# lps_display_rev_10_p1.net
KiCad netlist of a schematic drawn in Altium Designer
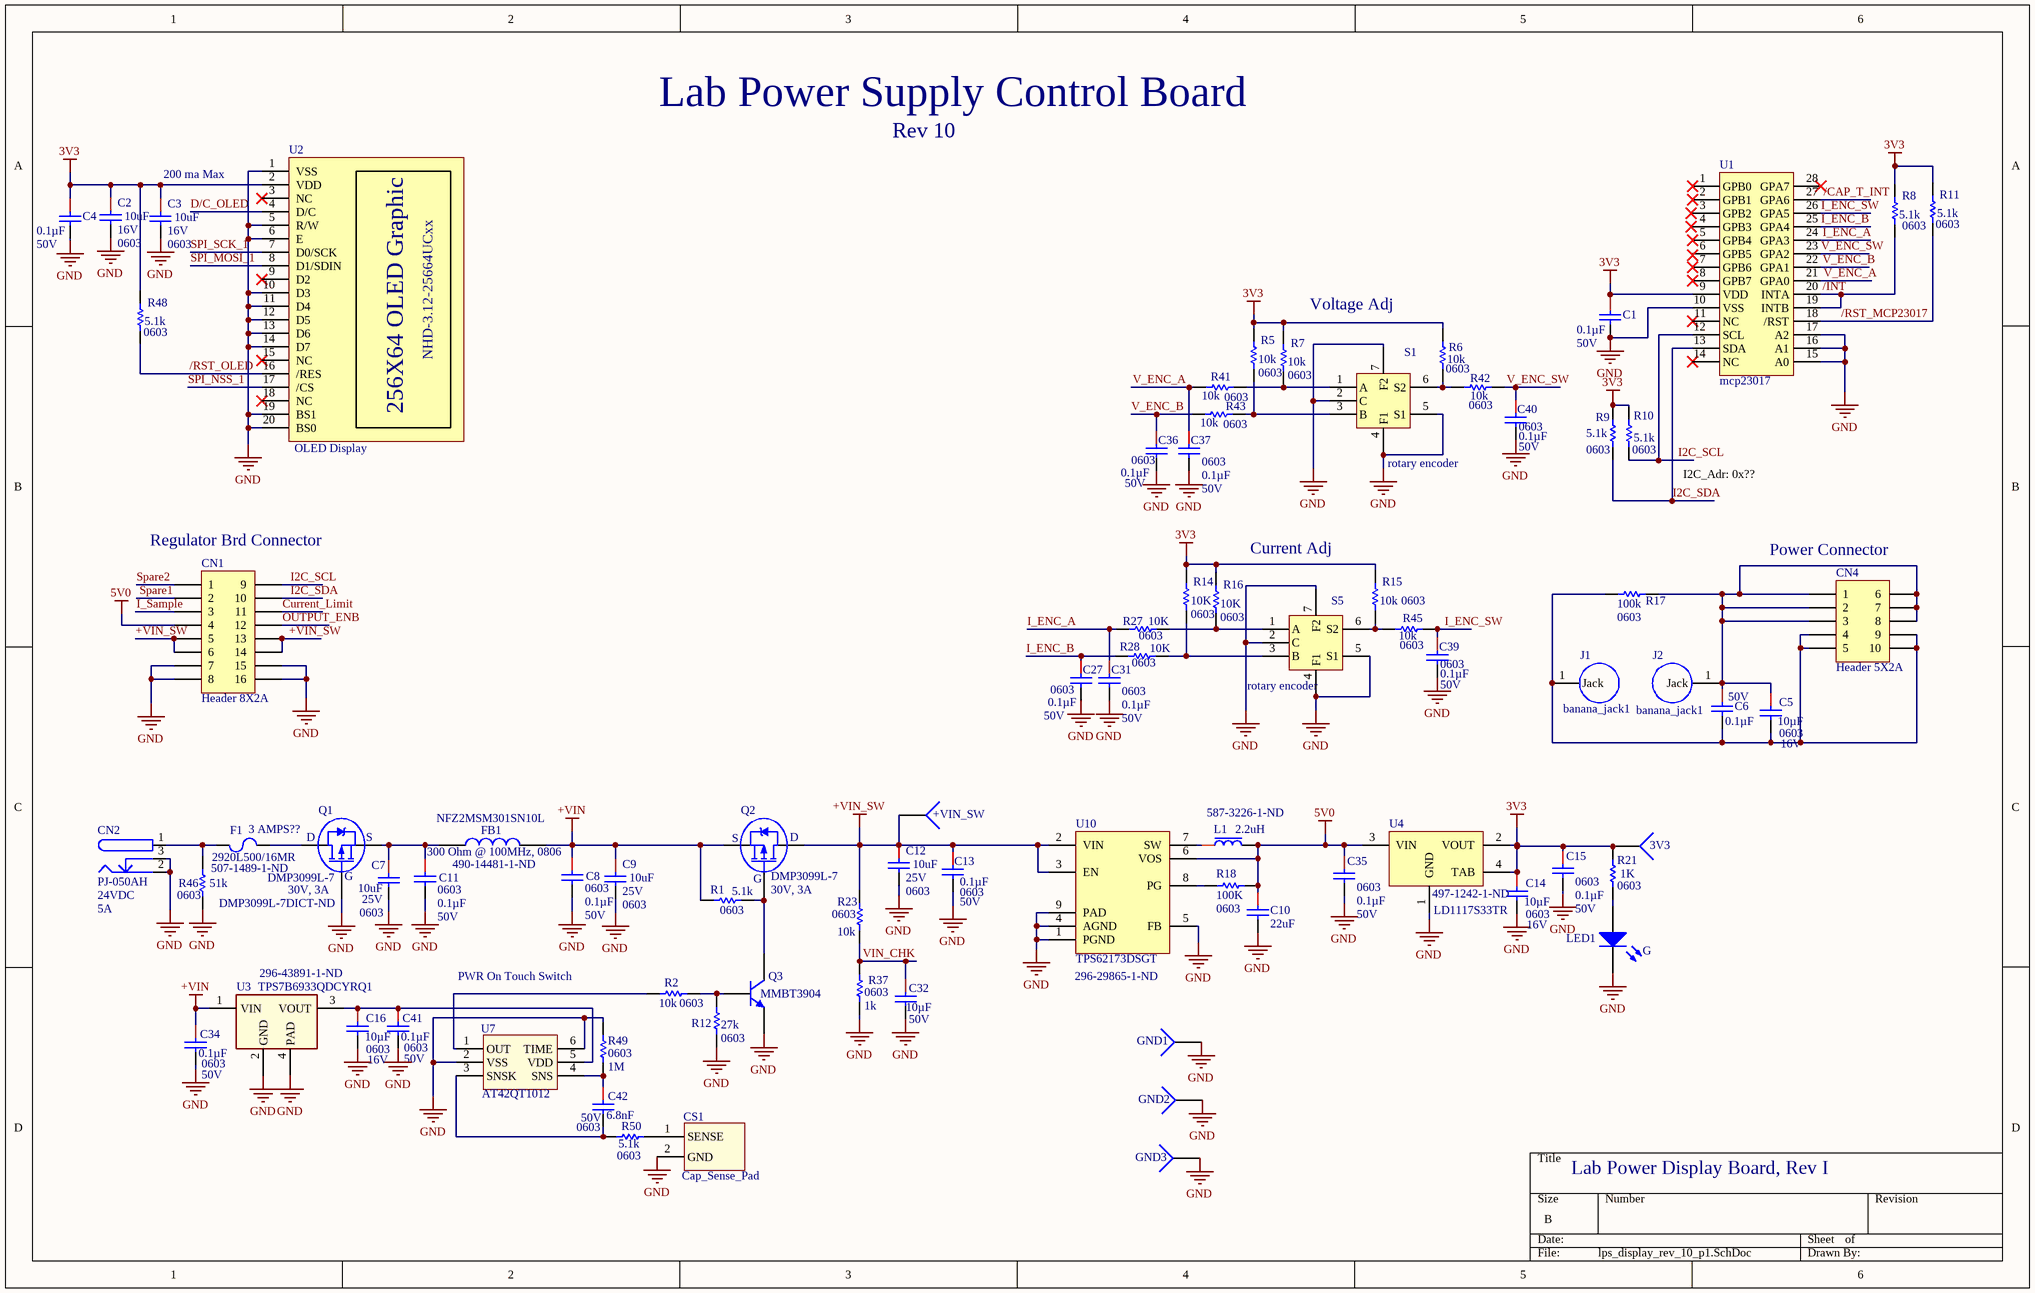
[diagram p0: lps_display_rev_10_p1.SchDoc]

(export (version "E")
  (design (tool "Eeschema 10.0.6"))
  (components
    (comp (ref "+VIN_SW")
      (value "~")
      (footprint "TestPoint-TH 35 mil")
      (description "Test Point")
      (libsource (lib "OLogic-Misc") (part "TestPoint"))
    )
    (comp (ref "3V3")
      (value "~")
      (footprint "TestPoint-TH 35 mil")
      (description "Test Point")
      (libsource (lib "OLogic-Misc") (part "TestPoint"))
    )
    (comp (ref "C1")
      (value "0.1uF 0603 50V")
      (footprint "CAPC0603(1608)_N")
      (fields
        (field (name "MANUFACTURER") "Kemet")
        (field (name "MANUFACTURER PART NUMBER") "C0603C104K5RACTU")
        (field (name "TOLERANCE") "±10%")
        (field (name "CAPACITANCE") "0.1µF")
        (field (name "VOLTAGE - RATED") "50V")
      )
      (libsource (lib "OLogic-Passive") (part "CAP CER 0.1UF 50V 10% X7R 0603"))
    )
    (comp (ref "C2")
      (value "10uF")
      (footprint "CAPC0603(1608)_N")
      (description "10UF 0603 16V")
      (fields
        (field (name "MANUFACTURER") "Murata Electronics North America")
        (field (name "MANUFACTURER PART NUMBER") "GRM188R61C106MA73D")
        (field (name "PACKAGE / CASE") "0603")
        (field (name "VOLTAGE - RATED") "16V")
      )
      (libsource (lib "OLogic-Passive") (part "CAP CER 10UF 16V 20% X5R 0603"))
    )
    (comp (ref "C3")
      (value "10uF")
      (footprint "CAPC0603(1608)_N")
      (description "10UF 0603 16V")
      (fields
        (field (name "MANUFACTURER") "Murata Electronics North America")
        (field (name "MANUFACTURER PART NUMBER") "GRM188R61C106MA73D")
        (field (name "PACKAGE / CASE") "0603")
        (field (name "VOLTAGE - RATED") "16V")
      )
      (libsource (lib "OLogic-Passive") (part "CAP CER 10UF 16V 20% X5R 0603"))
    )
    (comp (ref "C4")
      (value "0.1uF 0603 50V")
      (footprint "CAPC0603(1608)_N")
      (fields
        (field (name "MANUFACTURER") "Kemet")
        (field (name "MANUFACTURER PART NUMBER") "C0603C104K5RACTU")
        (field (name "TOLERANCE") "±10%")
        (field (name "CAPACITANCE") "0.1µF")
        (field (name "VOLTAGE - RATED") "50V")
      )
      (libsource (lib "OLogic-Passive") (part "CAP CER 0.1UF 50V 10% X7R 0603"))
    )
    (comp (ref "C5")
      (value "10uF")
      (footprint "CAPC0603(1608)_N")
      (description "10UF 0603 16V")
      (fields
        (field (name "MANUFACTURER") "Murata Electronics North America")
        (field (name "MANUFACTURER PART NUMBER") "GRM188R61C106MA73D")
        (field (name "CAPACITANCE") "10µF")
        (field (name "PACKAGE / CASE") "0603")
        (field (name "VOLTAGE - RATED") "16V")
      )
      (libsource (lib "OLogic-Passive") (part "CAP CER 10UF 16V 20% X5R 0603"))
    )
    (comp (ref "C6")
      (value "0.1uF 0603 50V")
      (footprint "CAPC0603(1608)_N")
      (fields
        (field (name "MANUFACTURER") "Kemet")
        (field (name "MANUFACTURER PART NUMBER") "C0603C104K5RACTU")
        (field (name "TOLERANCE") "±10%")
        (field (name "CAPACITANCE") "0.1µF")
        (field (name "VOLTAGE - RATED") "50V")
      )
      (libsource (lib "OLogic-Passive") (part "CAP CER 0.1UF 50V 10% X7R 0603"))
    )
    (comp (ref "C7")
      (value "10uF")
      (footprint "CAPC0603(1608)_N")
      (description "10UF 0603 16V")
      (fields
        (field (name "MANUFACTURER") "Murata Electronics North America")
        (field (name "MANUFACTURER PART NUMBER") "GRM188R61C106MA73D")
        (field (name "PACKAGE / CASE") "0603")
        (field (name "VOLTAGE - RATED") "25V")
      )
      (libsource (lib "OLogic-Passive") (part "CAP CER 10UF 16V 20% X5R 0603"))
    )
    (comp (ref "C8")
      (value "0.1uF 0603 50V")
      (footprint "CAPC0603(1608)_N")
      (fields
        (field (name "MANUFACTURER") "Yageo")
        (field (name "MANUFACTURER PART NUMBER") "CC0603ZRY5V9BB104")
        (field (name "TOLERANCE") "-20%, +80%")
        (field (name "PACKAGE / CASE") "0603")
        (field (name "CAPACITANCE") "0.1µF")
        (field (name "VOLTAGE - RATED") "50V")
      )
      (libsource (lib "OLogic-Passive") (part "CAP CER 0.1UF 50V 10% X7R 0603"))
    )
    (comp (ref "C9")
      (value "10uF")
      (footprint "CAPC0603(1608)_N")
      (description "10UF 0603 16V")
      (fields
        (field (name "MANUFACTURER") "Murata Electronics North America")
        (field (name "MANUFACTURER PART NUMBER") "GRM188R61C106MA73D")
        (field (name "PACKAGE / CASE") "0603")
        (field (name "VOLTAGE - RATED") "25V")
      )
      (libsource (lib "OLogic-Passive") (part "CAP CER 10UF 16V 20% X5R 0603"))
    )
    (comp (ref "C10")
      (value "22uF")
      (footprint "CAPC0603(1608)_M")
      (description "CAP CER 22UF 10V 20% 0603")
      (fields (field (name "TOLERANCE") "20%"))
      (libsource (lib "OLogic Nexus Vault") (part "=Capacitance"))
    )
    (comp (ref "C11")
      (value "0.1uF 0603 50V")
      (footprint "CAPC0603(1608)_N")
      (fields
        (field (name "MANUFACTURER") "Yageo")
        (field (name "MANUFACTURER PART NUMBER") "CC0603ZRY5V9BB104")
        (field (name "TOLERANCE") "-20%, +80%")
        (field (name "PACKAGE / CASE") "0603")
        (field (name "CAPACITANCE") "0.1µF")
        (field (name "VOLTAGE - RATED") "50V")
      )
      (libsource (lib "OLogic-Passive") (part "CAP CER 0.1UF 50V 10% X7R 0603"))
    )
    (comp (ref "C12")
      (value "10uF")
      (footprint "CAPC0603(1608)_N")
      (description "10UF 0603 16V")
      (fields
        (field (name "MANUFACTURER") "Murata Electronics North America")
        (field (name "MANUFACTURER PART NUMBER") "GRM188R61C106MA73D")
        (field (name "PACKAGE / CASE") "0603")
        (field (name "VOLTAGE - RATED") "25V")
      )
      (libsource (lib "OLogic-Passive") (part "CAP CER 10UF 16V 20% X5R 0603"))
    )
    (comp (ref "C13")
      (value "0.1uF 0603 50V")
      (footprint "CAPC0603(1608)_N")
      (fields
        (field (name "MANUFACTURER") "Yageo")
        (field (name "MANUFACTURER PART NUMBER") "CC0603ZRY5V9BB104")
        (field (name "TOLERANCE") "-20%, +80%")
        (field (name "PACKAGE / CASE") "0603")
        (field (name "CAPACITANCE") "0.1µF")
        (field (name "VOLTAGE - RATED") "50V")
      )
      (libsource (lib "OLogic-Passive") (part "CAP CER 0.1UF 50V 10% X7R 0603"))
    )
    (comp (ref "C14")
      (value "10uF")
      (footprint "CAPC0603(1608)_N")
      (description "10UF 0603 16V")
      (fields
        (field (name "MANUFACTURER") "Murata Electronics North America")
        (field (name "MANUFACTURER PART NUMBER") "GRM188R61C106MA73D")
        (field (name "CAPACITANCE") "10µF")
        (field (name "PACKAGE / CASE") "0603")
        (field (name "VOLTAGE - RATED") "16V")
      )
      (libsource (lib "OLogic-Passive") (part "CAP CER 10UF 16V 20% X5R 0603"))
    )
    (comp (ref "C15")
      (value "0.1uF 0603 50V")
      (footprint "CAPC0603(1608)_N")
      (fields
        (field (name "MANUFACTURER") "Yageo")
        (field (name "MANUFACTURER PART NUMBER") "CC0603ZRY5V9BB104")
        (field (name "TOLERANCE") "-20%, +80%")
        (field (name "PACKAGE / CASE") "0603")
        (field (name "CAPACITANCE") "0.1µF")
        (field (name "VOLTAGE - RATED") "50V")
      )
      (libsource (lib "OLogic-Passive") (part "CAP CER 0.1UF 50V 10% X7R 0603"))
    )
    (comp (ref "C16")
      (value "10uF")
      (footprint "CAPC0603(1608)_N")
      (description "10UF 0603 16V")
      (fields
        (field (name "MANUFACTURER") "Murata Electronics North America")
        (field (name "MANUFACTURER PART NUMBER") "GRM188R61C106MA73D")
        (field (name "CAPACITANCE") "10µF")
        (field (name "PACKAGE / CASE") "0603")
        (field (name "VOLTAGE - RATED") "16V")
      )
      (libsource (lib "OLogic-Passive") (part "CAP CER 10UF 16V 20% X5R 0603"))
    )
    (comp (ref "C27")
      (value "0.1uF 0603 50V")
      (footprint "CAPC0603(1608)_N")
      (fields
        (field (name "MANUFACTURER") "Yageo")
        (field (name "MANUFACTURER PART NUMBER") "CC0603ZRY5V9BB104")
        (field (name "TOLERANCE") "-20%, +80%")
        (field (name "PACKAGE / CASE") "0603")
        (field (name "CAPACITANCE") "0.1µF")
        (field (name "VOLTAGE - RATED") "50V")
      )
      (libsource (lib "OLogic-Passive") (part "CAP CER 0.1UF 50V 10% X7R 0603"))
    )
    (comp (ref "C31")
      (value "0.1uF 0603 50V")
      (footprint "CAPC0603(1608)_N")
      (fields
        (field (name "MANUFACTURER") "Yageo")
        (field (name "MANUFACTURER PART NUMBER") "CC0603ZRY5V9BB104")
        (field (name "TOLERANCE") "-20%, +80%")
        (field (name "PACKAGE / CASE") "0603")
        (field (name "CAPACITANCE") "0.1µF")
        (field (name "VOLTAGE - RATED") "50V")
      )
      (libsource (lib "OLogic-Passive") (part "CAP CER 0.1UF 50V 10% X7R 0603"))
    )
    (comp (ref "C32")
      (value "0.1uF 0603 50V")
      (footprint "CAPC0603(1608)_N")
      (fields
        (field (name "MANUFACTURER") "Kemet")
        (field (name "MANUFACTURER PART NUMBER") "C0603C104K5RACTU")
        (field (name "TOLERANCE") "±10%")
        (field (name "CAPACITANCE") "10µF")
        (field (name "VOLTAGE - RATED") "50V")
      )
      (libsource (lib "OLogic-Passive") (part "CAP CER 0.1UF 50V 10% X7R 0603"))
    )
    (comp (ref "C34")
      (value "0.1uF 0603 50V")
      (footprint "CAPC0603(1608)_N")
      (fields
        (field (name "MANUFACTURER") "Yageo")
        (field (name "MANUFACTURER PART NUMBER") "CC0603ZRY5V9BB104")
        (field (name "TOLERANCE") "-20%, +80%")
        (field (name "PACKAGE / CASE") "0603")
        (field (name "CAPACITANCE") "0.1µF")
        (field (name "VOLTAGE - RATED") "50V")
      )
      (libsource (lib "OLogic-Passive") (part "CAP CER 0.1UF 50V 10% X7R 0603"))
    )
    (comp (ref "C35")
      (value "0.1uF 0603 50V")
      (footprint "CAPC0603(1608)_N")
      (fields
        (field (name "MANUFACTURER") "Yageo")
        (field (name "MANUFACTURER PART NUMBER") "CC0603ZRY5V9BB104")
        (field (name "TOLERANCE") "-20%, +80%")
        (field (name "PACKAGE / CASE") "0603")
        (field (name "CAPACITANCE") "0.1µF")
        (field (name "VOLTAGE - RATED") "50V")
      )
      (libsource (lib "OLogic-Passive") (part "CAP CER 0.1UF 50V 10% X7R 0603"))
    )
    (comp (ref "C36")
      (value "0.1uF 0603 50V")
      (footprint "CAPC0603(1608)_N")
      (fields
        (field (name "MANUFACTURER") "Yageo")
        (field (name "MANUFACTURER PART NUMBER") "CC0603ZRY5V9BB104")
        (field (name "TOLERANCE") "-20%, +80%")
        (field (name "PACKAGE / CASE") "0603")
        (field (name "CAPACITANCE") "0.1µF")
        (field (name "VOLTAGE - RATED") "50V")
      )
      (libsource (lib "OLogic-Passive") (part "CAP CER 0.1UF 50V 10% X7R 0603"))
    )
    (comp (ref "C37")
      (value "0.1uF 0603 50V")
      (footprint "CAPC0603(1608)_N")
      (fields
        (field (name "MANUFACTURER") "Yageo")
        (field (name "MANUFACTURER PART NUMBER") "CC0603ZRY5V9BB104")
        (field (name "TOLERANCE") "-20%, +80%")
        (field (name "PACKAGE / CASE") "0603")
        (field (name "CAPACITANCE") "0.1µF")
        (field (name "VOLTAGE - RATED") "50V")
      )
      (libsource (lib "OLogic-Passive") (part "CAP CER 0.1UF 50V 10% X7R 0603"))
    )
    (comp (ref "C39")
      (value "0.1uF 0603 50V")
      (footprint "CAPC0603(1608)_N")
      (fields
        (field (name "MANUFACTURER") "Yageo")
        (field (name "MANUFACTURER PART NUMBER") "CC0603ZRY5V9BB104")
        (field (name "TOLERANCE") "-20%, +80%")
        (field (name "PACKAGE / CASE") "0603")
        (field (name "CAPACITANCE") "0.1µF")
        (field (name "VOLTAGE - RATED") "50V")
      )
      (libsource (lib "OLogic-Passive") (part "CAP CER 0.1UF 50V 10% X7R 0603"))
    )
    (comp (ref "C40")
      (value "0.1uF 0603 50V")
      (footprint "CAPC0603(1608)_N")
      (fields
        (field (name "MANUFACTURER") "Yageo")
        (field (name "MANUFACTURER PART NUMBER") "CC0603ZRY5V9BB104")
        (field (name "TOLERANCE") "-20%, +80%")
        (field (name "PACKAGE / CASE") "0603")
        (field (name "CAPACITANCE") "0.1µF")
        (field (name "VOLTAGE - RATED") "50V")
      )
      (libsource (lib "OLogic-Passive") (part "CAP CER 0.1UF 50V 10% X7R 0603"))
    )
    (comp (ref "C41")
      (value "0.1uF 0603 50V")
      (footprint "CAPC0603(1608)_N")
      (fields
        (field (name "MANUFACTURER") "Yageo")
        (field (name "MANUFACTURER PART NUMBER") "CC0603ZRY5V9BB104")
        (field (name "TOLERANCE") "-20%, +80%")
        (field (name "PACKAGE / CASE") "0603")
        (field (name "CAPACITANCE") "0.1µF")
        (field (name "VOLTAGE - RATED") "50V")
      )
      (libsource (lib "OLogic-Passive") (part "CAP CER 0.1UF 50V 10% X7R 0603"))
    )
    (comp (ref "C42")
      (value "0.1uF 0603 50V")
      (footprint "CAPC0603(1608)_N")
      (fields
        (field (name "MANUFACTURER") "Yageo")
        (field (name "MANUFACTURER PART NUMBER") "CC0603ZRY5V9BB104")
        (field (name "TOLERANCE") "-20%, +80%")
        (field (name "PACKAGE / CASE") "0603")
        (field (name "CAPACITANCE") "6.8nF")
        (field (name "VOLTAGE - RATED") "50V")
      )
      (libsource (lib "OLogic-Passive") (part "CAP CER 0.1UF 50V 10% X7R 0603"))
    )
    (comp (ref "CN1")
      (value "Header 8X2A")
      (footprint "HDR2X8_CEN")
      (description "Header, 8-Pin, Dual row")
      (fields (field (name "PUBLISHER") "Altium Limited"))
      (libsource (lib "OLogic Nexus Vault") (part "Header 8X2A"))
    )
    (comp (ref "CN2")
      (value "PJ-050AH")
      (footprint "PJ-050AH")
      (description "Power Barrel Connector Jack 2.00mm ID 5.50mm OD Through Hole, Right Angle")
      (fields
        (field (name "VOLTAGE - RATED") "24VDC")
        (field (name "CURRENT RATING") "5A")
        (field (name "MANUFACTURER") "CUI")
      )
      (libsource (lib "OLogic Nexus Vault") (part "PJ-050AH"))
    )
    (comp (ref "CN4")
      (value "Header 5X2A")
      (footprint "HDR2X5_CEN")
      (description "Header, 5-Pin, Dual row")
      (fields (field (name "PUBLISHER") "Altium Limited"))
      (libsource (lib "OLogic Nexus Vault") (part "Header 5X2A"))
    )
    (comp (ref "CS1")
      (value "Cap_Sense_Pad")
      (footprint "CAP_TOUCH_ROUND")
      (libsource (lib "*") (part "Cap_Sense_Pad"))
    )
    (comp (ref "F1")
      (value "2920L500/16MR")
      (footprint "2920 Fuse")
      (description "PTC RESET FUSE 16V 5A 2920")
      (libsource (lib "OLogic Nexus Vault") (part "FUSE_GENERIC"))
    )
    (comp (ref "FB1")
      (value "300 Ohm @ 100MHz, 0806")
      (footprint "RESC0805(2012)_M")
      (description "40 OHM 0805 1.5A")
      (fields
        (field (name "MANUFACTURER") "Laird-Signal Integrity Products")
        (field (name "MANUFACTURER PART NUMBER") "MI0805K400R-10")
        (field (name "CREATOR") "osman")
      )
      (libsource (lib "OLogic-Passive") (part "FERRITE 40 OHM 1.5A 0805"))
    )
    (comp (ref "GND1")
      (value "~")
      (footprint "TestPoint-TH 35 mil")
      (description "Test Point")
      (libsource (lib "OLogic-Misc") (part "TestPoint"))
    )
    (comp (ref "GND2")
      (value "~")
      (footprint "TestPoint-TH 35 mil")
      (description "Test Point")
      (libsource (lib "OLogic-Misc") (part "TestPoint"))
    )
    (comp (ref "GND3")
      (value "~")
      (footprint "TestPoint-TH 35 mil")
      (description "Test Point")
      (libsource (lib "OLogic-Misc") (part "TestPoint"))
    )
    (comp (ref "J1")
      (value "banana_jack1")
      (footprint "Banana_jack1")
      (libsource (lib "lab power supply") (part "banana_jack1"))
    )
    (comp (ref "J2")
      (value "banana_jack1")
      (footprint "Banana_jack1")
      (libsource (lib "lab power supply") (part "banana_jack1"))
    )
    (comp (ref "L1")
      (value "2.2uH")
      (footprint "INDC2520X10N")
      (description "FIXED IND 2.2UH 1.9A 117 MOHM")
      (fields (field (name "TOLERANCE") "20%"))
      (libsource (lib "OLogic Nexus Vault") (part "IND_GENERIC"))
    )
    (comp (ref "LED1")
      (value "G")
      (footprint "SM-LED-0603")
      (description "0603 SMD LED")
      (libsource (lib "OLogic-Diode-Opto-LED") (part "0603 LED"))
    )
    (comp (ref "Q1")
      (value "DMP3099L-7")
      (footprint "SOT23")
      (description "DMP3099L-7 MOSFET P-CH SOT23")
      (fields (field (name "MANUFACTURER") "Diodes Incorporated") (field (name "TEXT") "30V, 3A"))
      (libsource (lib "") (part "DMP3099L-7_1"))
    )
    (comp (ref "Q2")
      (value "DMP3099L-7")
      (footprint "SOT23")
      (description "DMP3099L-7 MOSFET P-CH SOT23")
      (fields (field (name "MANUFACTURER") "Diodes Incorporated") (field (name "TEXT") "30V, 3A"))
      (libsource (lib "OLogic-Trans-Drivers") (part "DMP3099L-7"))
    )
    (comp (ref "Q3")
      (value "MMBT3904")
      (footprint "SOT23")
      (description "MMBT3904 NPN")
      (fields (field (name "MANUFACTURER") "ON Semiconductor") (field (name "MPN") "MMBT3904WT1G"))
      (libsource (lib "OLogic-Trans-Drivers") (part "MMBT3904"))
    )
    (comp (ref "R1")
      (value "4.7K")
      (footprint "RESC0603(1608)_N")
      (description "4.7K 0603")
      (fields
        (field (name "MANUFACTURER") "Panasonic Electronic Components")
        (field (name "MANUFACTURER PART NUMBER") "ERJ-3GEYJ472V")
        (field (name "RESISTANCE (OHMS)") "5.1k")
        (field (name "PACKAGE / CASE") "0603")
      )
      (libsource (lib "OLogic-Passive") (part "RES 4.7K OHM 1/10W 5% 0603 SMD"))
    )
    (comp (ref "R2")
      (value "4.7K")
      (footprint "RESC0603(1608)_N")
      (description "4.7K 0603")
      (fields
        (field (name "MANUFACTURER") "Panasonic Electronic Components")
        (field (name "MANUFACTURER PART NUMBER") "ERJ-3GEYJ472V")
        (field (name "RESISTANCE (OHMS)") "10k")
        (field (name "PACKAGE / CASE") "0603")
      )
      (libsource (lib "OLogic-Passive") (part "RES 4.7K OHM 1/10W 5% 0603 SMD"))
    )
    (comp (ref "R5")
      (value "4.7K")
      (footprint "RESC0603(1608)_N")
      (description "4.7K 0603")
      (fields
        (field (name "MANUFACTURER") "Panasonic Electronic Components")
        (field (name "MANUFACTURER PART NUMBER") "ERJ-3GEYJ472V")
        (field (name "RESISTANCE (OHMS)") "10k")
        (field (name "PACKAGE / CASE") "0603")
      )
      (libsource (lib "OLogic-Passive") (part "RES 4.7K OHM 1/10W 5% 0603 SMD"))
    )
    (comp (ref "R6")
      (value "4.7K")
      (footprint "RESC0603(1608)_N")
      (description "4.7K 0603")
      (fields
        (field (name "MANUFACTURER") "Panasonic Electronic Components")
        (field (name "MANUFACTURER PART NUMBER") "ERJ-3GEYJ472V")
        (field (name "RESISTANCE (OHMS)") "10k")
        (field (name "PACKAGE / CASE") "0603")
      )
      (libsource (lib "OLogic-Passive") (part "RES 4.7K OHM 1/10W 5% 0603 SMD"))
    )
    (comp (ref "R7")
      (value "4.7K")
      (footprint "RESC0603(1608)_N")
      (description "4.7K 0603")
      (fields
        (field (name "MANUFACTURER") "Panasonic Electronic Components")
        (field (name "MANUFACTURER PART NUMBER") "ERJ-3GEYJ472V")
        (field (name "RESISTANCE (OHMS)") "10k")
        (field (name "PACKAGE / CASE") "0603")
      )
      (libsource (lib "OLogic-Passive") (part "RES 4.7K OHM 1/10W 5% 0603 SMD"))
    )
    (comp (ref "R8")
      (value "4.7K")
      (footprint "RESC0603(1608)_N")
      (description "4.7K 0603")
      (fields
        (field (name "MANUFACTURER") "Panasonic Electronic Components")
        (field (name "MANUFACTURER PART NUMBER") "ERJ-3GEYJ472V")
        (field (name "RESISTANCE (OHMS)") "5.1k")
        (field (name "PACKAGE / CASE") "0603")
      )
      (libsource (lib "OLogic-Passive") (part "RES 4.7K OHM 1/10W 5% 0603 SMD"))
    )
    (comp (ref "R9")
      (value "4.7K")
      (footprint "RESC0603(1608)_N")
      (description "4.7K 0603")
      (fields
        (field (name "MANUFACTURER") "Panasonic Electronic Components")
        (field (name "MANUFACTURER PART NUMBER") "ERJ-3GEYJ472V")
        (field (name "RESISTANCE (OHMS)") "5.1k")
        (field (name "PACKAGE / CASE") "0603")
      )
      (libsource (lib "OLogic-Passive") (part "RES 4.7K OHM 1/10W 5% 0603 SMD"))
    )
    (comp (ref "R10")
      (value "4.7K")
      (footprint "RESC0603(1608)_N")
      (description "4.7K 0603")
      (fields
        (field (name "MANUFACTURER") "Panasonic Electronic Components")
        (field (name "MANUFACTURER PART NUMBER") "ERJ-3GEYJ472V")
        (field (name "RESISTANCE (OHMS)") "5.1k")
        (field (name "PACKAGE / CASE") "0603")
      )
      (libsource (lib "OLogic-Passive") (part "RES 4.7K OHM 1/10W 5% 0603 SMD"))
    )
    (comp (ref "R11")
      (value "4.7K")
      (footprint "RESC0603(1608)_N")
      (description "4.7K 0603")
      (fields
        (field (name "MANUFACTURER") "Panasonic Electronic Components")
        (field (name "MANUFACTURER PART NUMBER") "ERJ-3GEYJ472V")
        (field (name "RESISTANCE (OHMS)") "5.1k")
        (field (name "PACKAGE / CASE") "0603")
      )
      (libsource (lib "OLogic-Passive") (part "RES 4.7K OHM 1/10W 5% 0603 SMD"))
    )
    (comp (ref "R12")
      (value "4.7K")
      (footprint "RESC0603(1608)_N")
      (description "4.7K 0603")
      (fields
        (field (name "MANUFACTURER") "Panasonic Electronic Components")
        (field (name "MANUFACTURER PART NUMBER") "ERJ-3GEYJ472V")
        (field (name "RESISTANCE (OHMS)") "27k")
        (field (name "PACKAGE / CASE") "0603")
      )
      (libsource (lib "OLogic-Passive") (part "RES 4.7K OHM 1/10W 5% 0603 SMD"))
    )
    (comp (ref "R14")
      (value "4.7K")
      (footprint "RESC0603(1608)_N")
      (description "4.7K 0603")
      (fields
        (field (name "MANUFACTURER") "Panasonic Electronic Components")
        (field (name "MANUFACTURER PART NUMBER") "ERJ-3GEYJ472V")
        (field (name "RESISTANCE (OHMS)") "10K")
        (field (name "PACKAGE / CASE") "0603")
      )
      (libsource (lib "OLogic-Passive") (part "RES 4.7K OHM 1/10W 5% 0603 SMD"))
    )
    (comp (ref "R15")
      (value "4.7K")
      (footprint "RESC0603(1608)_N")
      (description "4.7K 0603")
      (fields
        (field (name "MANUFACTURER") "Panasonic Electronic Components")
        (field (name "MANUFACTURER PART NUMBER") "ERJ-3GEYJ472V")
        (field (name "RESISTANCE (OHMS)") "10k")
        (field (name "PACKAGE / CASE") "0603")
      )
      (libsource (lib "OLogic-Passive") (part "RES 4.7K OHM 1/10W 5% 0603 SMD"))
    )
    (comp (ref "R16")
      (value "4.7K")
      (footprint "RESC0603(1608)_N")
      (description "4.7K 0603")
      (fields
        (field (name "MANUFACTURER") "Panasonic Electronic Components")
        (field (name "MANUFACTURER PART NUMBER") "ERJ-3GEYJ472V")
        (field (name "RESISTANCE (OHMS)") "10K")
        (field (name "PACKAGE / CASE") "0603")
      )
      (libsource (lib "OLogic-Passive") (part "RES 4.7K OHM 1/10W 5% 0603 SMD"))
    )
    (comp (ref "R17")
      (value "4.7K")
      (footprint "RESC0603(1608)_N")
      (description "4.7K 0603")
      (fields
        (field (name "MANUFACTURER") "Panasonic Electronic Components")
        (field (name "MANUFACTURER PART NUMBER") "ERJ-3GEYJ472V")
        (field (name "RESISTANCE (OHMS)") "100k")
        (field (name "PACKAGE / CASE") "0603")
      )
      (libsource (lib "OLogic-Passive") (part "RES 4.7K OHM 1/10W 5% 0603 SMD"))
    )
    (comp (ref "R18")
      (value "100K")
      (footprint "RESC0603(1608)_N")
      (description "100K 0603")
      (fields
        (field (name "MANUFACTURER") "Yageo")
        (field (name "MANUFACTURER PART NUMBER") "RC0603FR-07100KL")
        (field (name "SUPPLIER DEVICE PACKAGE") "0603")
      )
      (libsource (lib "OLogic-Passive") (part "RES 100K OHM 1% 1/10W 0603"))
    )
    (comp (ref "R21")
      (value "4.7K")
      (footprint "RESC0603(1608)_N")
      (description "4.7K 0603")
      (fields
        (field (name "MANUFACTURER") "Panasonic Electronic Components")
        (field (name "MANUFACTURER PART NUMBER") "ERJ-3GEYJ472V")
        (field (name "RESISTANCE (OHMS)") "1K")
        (field (name "PACKAGE / CASE") "0603")
      )
      (libsource (lib "OLogic-Passive") (part "RES 4.7K OHM 1/10W 5% 0603 SMD"))
    )
    (comp (ref "R23")
      (value "1.0K")
      (footprint "RESC0603(1608)_N")
      (description "1.0K 0603")
      (fields
        (field (name "MANUFACTURER") "Stackpole Electronics Inc.")
        (field (name "MANUFACTURER PART NUMBER") "RMCF0603FT1K00")
        (field (name "PACKAGE / CASE") "0603")
        (field (name "RESISTANCE (OHMS)") "10k")
      )
      (libsource (lib "OLogic-Passive") (part "RES 1K OHM 1% 1/10W 0603"))
    )
    (comp (ref "R27")
      (value "4.7K")
      (footprint "RESC0603(1608)_N")
      (description "4.7K 0603")
      (fields
        (field (name "MANUFACTURER") "Panasonic Electronic Components")
        (field (name "MANUFACTURER PART NUMBER") "ERJ-3GEYJ472V")
        (field (name "RESISTANCE (OHMS)") "10K")
        (field (name "PACKAGE / CASE") "0603")
      )
      (libsource (lib "OLogic-Passive") (part "RES 4.7K OHM 1/10W 5% 0603 SMD"))
    )
    (comp (ref "R28")
      (value "4.7K")
      (footprint "RESC0603(1608)_N")
      (description "4.7K 0603")
      (fields
        (field (name "MANUFACTURER") "Panasonic Electronic Components")
        (field (name "MANUFACTURER PART NUMBER") "ERJ-3GEYJ472V")
        (field (name "RESISTANCE (OHMS)") "10K")
        (field (name "PACKAGE / CASE") "0603")
      )
      (libsource (lib "OLogic-Passive") (part "RES 4.7K OHM 1/10W 5% 0603 SMD"))
    )
    (comp (ref "R37")
      (value "1.0K")
      (footprint "RESC0603(1608)_N")
      (description "1.0K 0603")
      (fields
        (field (name "MANUFACTURER") "Stackpole Electronics Inc.")
        (field (name "MANUFACTURER PART NUMBER") "RMCF0603FT1K00")
        (field (name "PACKAGE / CASE") "0603")
        (field (name "RESISTANCE (OHMS)") "1k")
      )
      (libsource (lib "OLogic-Passive") (part "RES 1K OHM 1% 1/10W 0603"))
    )
    (comp (ref "R41")
      (value "4.7K")
      (footprint "RESC0603(1608)_N")
      (description "4.7K 0603")
      (fields
        (field (name "MANUFACTURER") "Panasonic Electronic Components")
        (field (name "MANUFACTURER PART NUMBER") "ERJ-3GEYJ472V")
        (field (name "RESISTANCE (OHMS)") "10k")
        (field (name "PACKAGE / CASE") "0603")
      )
      (libsource (lib "OLogic-Passive") (part "RES 4.7K OHM 1/10W 5% 0603 SMD"))
    )
    (comp (ref "R42")
      (value "4.7K")
      (footprint "RESC0603(1608)_N")
      (description "4.7K 0603")
      (fields
        (field (name "MANUFACTURER") "Panasonic Electronic Components")
        (field (name "MANUFACTURER PART NUMBER") "ERJ-3GEYJ472V")
        (field (name "RESISTANCE (OHMS)") "10k")
        (field (name "PACKAGE / CASE") "0603")
      )
      (libsource (lib "OLogic-Passive") (part "RES 4.7K OHM 1/10W 5% 0603 SMD"))
    )
    (comp (ref "R43")
      (value "4.7K")
      (footprint "RESC0603(1608)_N")
      (description "4.7K 0603")
      (fields
        (field (name "MANUFACTURER") "Panasonic Electronic Components")
        (field (name "MANUFACTURER PART NUMBER") "ERJ-3GEYJ472V")
        (field (name "RESISTANCE (OHMS)") "10k")
        (field (name "PACKAGE / CASE") "0603")
      )
      (libsource (lib "OLogic-Passive") (part "RES 4.7K OHM 1/10W 5% 0603 SMD"))
    )
    (comp (ref "R45")
      (value "4.7K")
      (footprint "RESC0603(1608)_N")
      (description "4.7K 0603")
      (fields
        (field (name "MANUFACTURER") "Panasonic Electronic Components")
        (field (name "MANUFACTURER PART NUMBER") "ERJ-3GEYJ472V")
        (field (name "RESISTANCE (OHMS)") "10k")
        (field (name "PACKAGE / CASE") "0603")
      )
      (libsource (lib "OLogic-Passive") (part "RES 4.7K OHM 1/10W 5% 0603 SMD"))
    )
    (comp (ref "R46")
      (value "1.0K")
      (footprint "RESC0603(1608)_N")
      (description "1.0K 0603")
      (fields
        (field (name "MANUFACTURER") "Stackpole Electronics Inc.")
        (field (name "MANUFACTURER PART NUMBER") "RMCF0603FT1K00")
        (field (name "PACKAGE / CASE") "0603")
        (field (name "RESISTANCE (OHMS)") "51k")
      )
      (libsource (lib "OLogic-Passive") (part "RES 1K OHM 1% 1/10W 0603"))
    )
    (comp (ref "R48")
      (value "4.7K")
      (footprint "RESC0603(1608)_N")
      (description "4.7K 0603")
      (fields
        (field (name "MANUFACTURER") "Panasonic Electronic Components")
        (field (name "MANUFACTURER PART NUMBER") "ERJ-3GEYJ472V")
        (field (name "RESISTANCE (OHMS)") "5.1k")
        (field (name "PACKAGE / CASE") "0603")
      )
      (libsource (lib "OLogic-Passive") (part "RES 4.7K OHM 1/10W 5% 0603 SMD"))
    )
    (comp (ref "R49")
      (value "1.0K")
      (footprint "RESC0603(1608)_N")
      (description "1.0K 0603")
      (fields
        (field (name "MANUFACTURER") "Stackpole Electronics Inc.")
        (field (name "MANUFACTURER PART NUMBER") "RMCF0603FT1K00")
        (field (name "PACKAGE / CASE") "0603")
        (field (name "RESISTANCE (OHMS)") "1M")
      )
      (libsource (lib "OLogic-Passive") (part "RES 1K OHM 1% 1/10W 0603"))
    )
    (comp (ref "R50")
      (value "1.0K")
      (footprint "RESC0603(1608)_N")
      (description "1.0K 0603")
      (fields
        (field (name "MANUFACTURER") "Stackpole Electronics Inc.")
        (field (name "MANUFACTURER PART NUMBER") "RMCF0603FT1K00")
        (field (name "PACKAGE / CASE") "0603")
        (field (name "RESISTANCE (OHMS)") "5.1k")
      )
      (libsource (lib "OLogic-Passive") (part "RES 1K OHM 1% 1/10W 0603"))
    )
    (comp (ref "S1")
      (value "rotary encoder")
      (footprint "rotary encoder")
      (libsource (lib "hdmi_lvds") (part "rotary encoder"))
    )
    (comp (ref "S5")
      (value "rotary encoder")
      (footprint "rotary encoder")
      (libsource (lib "hdmi_lvds") (part "rotary encoder"))
    )
    (comp (ref "U1")
      (value "mcp23017")
      (footprint "SOIC28")
      (description "I2C 16 bit Expander")
      (libsource (lib "hdmi_lvds") (part "mcp23017"))
    )
    (comp (ref "U2")
      (value "OLED Display")
      (footprint "oled_graphic_256X64")
      (libsource (lib "*") (part "OLED_Graphic_240x64"))
    )
    (comp (ref "U3")
      (value "TPS7B6933QDCYRQ1")
      (footprint "SOT-223")
      (libsource (lib "*") (part "TPS7B6933QDCYQ1"))
    )
    (comp (ref "U4")
      (value "3.3V")
      (footprint "DSO-G3")
      (description "3.3 volt fixed regulator, 800mA")
      (fields (field (name "SUPPLIER PART NUMBER 1") "497-1242-1-ND"))
      (libsource (lib "OLogic-Reg-Convert") (part "LD1117S33"))
    )
    (comp (ref "U7")
      (value "AT42QT1012")
      (footprint "SOt-23-6")
      (description "CAP QTouch Chip")
      (libsource (lib "*") (part "AT42QT1012"))
    )
    (comp (ref "U10")
      (value "TPS62173DSGT")
      (footprint "WSON(8) 2mm x 2mm")
      (description "IC REG BUCK ADJ 0.5A SYNC 8WSON")
      (libsource (lib "OLogic Nexus Vault") (part "TPS62170DSGR"))
    )
  )
  (nets
    (net (code "1") (name "+VIN") (class "Default")
      (node (ref "C34") (pin "1") (pinfunction "1_1") (pintype "passive"))
      (node (ref "C8") (pin "1") (pinfunction "1_1") (pintype "passive"))
      (node (ref "C9") (pin "1") (pinfunction "1_1") (pintype "passive"))
      (node (ref "FB1") (pin "2") (pinfunction "2_2") (pintype "passive"))
      (node (ref "Q2") (pin "2") (pinfunction "S_2") (pintype "passive"))
      (node (ref "R1") (pin "2") (pinfunction "2_2") (pintype "passive"))
      (node (ref "U3") (pin "1") (pinfunction "VIN_1") (pintype "power_in"))
    )
    (net (code "2") (name "+VIN_SW") (class "Default")
      (node (ref "+VIN_SW") (pin "1") (pinfunction "1_1") (pintype "passive"))
      (node (ref "C12") (pin "1") (pinfunction "1_1") (pintype "passive"))
      (node (ref "C13") (pin "1") (pinfunction "1_1") (pintype "passive"))
      (node (ref "CN1") (pin "13") (pinfunction "13_13") (pintype "passive"))
      (node (ref "CN1") (pin "14") (pinfunction "14_14") (pintype "passive"))
      (node (ref "CN1") (pin "5") (pinfunction "5_5") (pintype "passive"))
      (node (ref "CN1") (pin "6") (pinfunction "6_6") (pintype "passive"))
      (node (ref "Q2") (pin "3") (pinfunction "D_3") (pintype "passive"))
      (node (ref "R23") (pin "2") (pinfunction "2_2") (pintype "passive"))
      (node (ref "U10") (pin "2") (pinfunction "VIN_2") (pintype "power_in"))
      (node (ref "U10") (pin "3") (pinfunction "EN_3") (pintype "passive"))
    )
    (net (code "3") (name "/Current_Limit") (class "Default")
      (node (ref "CN1") (pin "11") (pinfunction "11_11") (pintype "passive"))
    )
    (net (code "4") (name "/D{slash}C_OLED") (class "Default")
      (node (ref "U2") (pin "4") (pinfunction "D/C_4") (pintype "passive"))
    )
    (net (code "5") (name "/I2C_SCL") (class "Default")
      (node (ref "CN1") (pin "9") (pinfunction "9_9") (pintype "passive"))
      (node (ref "R10") (pin "1") (pinfunction "1_1") (pintype "passive"))
      (node (ref "U1") (pin "12") (pinfunction "SCL_12") (pintype "passive"))
    )
    (net (code "6") (name "/I2C_SDA") (class "Default")
      (node (ref "CN1") (pin "10") (pinfunction "10_10") (pintype "passive"))
      (node (ref "R9") (pin "1") (pinfunction "1_1") (pintype "passive"))
      (node (ref "U1") (pin "13") (pinfunction "SDA_13") (pintype "passive"))
    )
    (net (code "7") (name "/I_ENC_A") (class "Default")
      (node (ref "C31") (pin "1") (pinfunction "1_1") (pintype "passive"))
      (node (ref "R27") (pin "2") (pinfunction "2_2") (pintype "passive"))
      (node (ref "U1") (pin "24") (pinfunction "GPA3_24") (pintype "passive"))
    )
    (net (code "8") (name "/I_ENC_B") (class "Default")
      (node (ref "C27") (pin "1") (pinfunction "1_1") (pintype "passive"))
      (node (ref "R28") (pin "2") (pinfunction "2_2") (pintype "passive"))
      (node (ref "U1") (pin "25") (pinfunction "GPA4_25") (pintype "passive"))
    )
    (net (code "9") (name "/I_ENC_SW") (class "Default")
      (node (ref "C39") (pin "1") (pinfunction "1_1") (pintype "passive"))
      (node (ref "R45") (pin "1") (pinfunction "1_1") (pintype "passive"))
      (node (ref "U1") (pin "26") (pinfunction "GPA5_26") (pintype "passive"))
    )
    (net (code "10") (name "/I_Sample") (class "Default")
      (node (ref "CN1") (pin "3") (pinfunction "3_3") (pintype "passive"))
    )
    (net (code "11") (name "/OUTPUT_ENB") (class "Default")
      (node (ref "CN1") (pin "12") (pinfunction "12_12") (pintype "passive"))
    )
    (net (code "12") (name "/SPI_MOSI_1") (class "Default")
      (node (ref "U2") (pin "8") (pinfunction "D1/SDIN_8") (pintype "passive"))
    )
    (net (code "13") (name "/SPI_NSS_1") (class "Default")
      (node (ref "U2") (pin "17") (pinfunction "/CS_17") (pintype "passive"))
    )
    (net (code "14") (name "/SPI_SCK_1") (class "Default")
      (node (ref "U2") (pin "7") (pinfunction "D0/SCK_7") (pintype "passive"))
    )
    (net (code "15") (name "/Spare1") (class "Default")
      (node (ref "CN1") (pin "2") (pinfunction "2_2") (pintype "passive"))
    )
    (net (code "16") (name "/Spare2") (class "Default")
      (node (ref "CN1") (pin "1") (pinfunction "1_1") (pintype "passive"))
    )
    (net (code "17") (name "/VIN_CHK") (class "Default")
      (node (ref "C32") (pin "1") (pinfunction "1_1") (pintype "passive"))
      (node (ref "R23") (pin "1") (pinfunction "1_1") (pintype "passive"))
      (node (ref "R37") (pin "2") (pinfunction "2_2") (pintype "passive"))
    )
    (net (code "18") (name "/V_ENC_A") (class "Default")
      (node (ref "C37") (pin "1") (pinfunction "1_1") (pintype "passive"))
      (node (ref "R41") (pin "2") (pinfunction "2_2") (pintype "passive"))
      (node (ref "U1") (pin "21") (pinfunction "GPA0_21") (pintype "passive"))
    )
    (net (code "19") (name "/V_ENC_B") (class "Default")
      (node (ref "C36") (pin "1") (pinfunction "1_1") (pintype "passive"))
      (node (ref "R43") (pin "2") (pinfunction "2_2") (pintype "passive"))
      (node (ref "U1") (pin "22") (pinfunction "GPA1_22") (pintype "passive"))
    )
    (net (code "20") (name "/V_ENC_SW") (class "Default")
      (node (ref "C40") (pin "1") (pinfunction "1_1") (pintype "passive"))
      (node (ref "R42") (pin "1") (pinfunction "1_1") (pintype "passive"))
      (node (ref "U1") (pin "23") (pinfunction "GPA2_23") (pintype "passive"))
    )
    (net (code "21") (name "/{slash}CAP_T_INT") (class "Default")
      (node (ref "U1") (pin "27") (pinfunction "GPA6_27") (pintype "passive"))
    )
    (net (code "22") (name "/{slash}INT") (class "Default")
      (node (ref "R8") (pin "1") (pinfunction "1_1") (pintype "passive"))
      (node (ref "U1") (pin "19") (pinfunction "INTB_19") (pintype "passive"))
      (node (ref "U1") (pin "20") (pinfunction "INTA_20") (pintype "passive"))
    )
    (net (code "23") (name "/{slash}RST_MCP23017") (class "Default")
      (node (ref "R11") (pin "1") (pinfunction "1_1") (pintype "passive"))
      (node (ref "U1") (pin "18") (pinfunction "/RST_18") (pintype "passive"))
    )
    (net (code "24") (name "/{slash}RST_OLED") (class "Default")
      (node (ref "R48") (pin "1") (pinfunction "1_1") (pintype "passive"))
      (node (ref "U2") (pin "16") (pinfunction "/RES_16") (pintype "passive"))
    )
    (net (code "25") (name "3V3") (class "Default")
      (node (ref "3V3") (pin "1") (pinfunction "1_1") (pintype "passive"))
      (node (ref "C1") (pin "1") (pinfunction "1_1") (pintype "passive"))
      (node (ref "C14") (pin "1") (pinfunction "1_1") (pintype "passive"))
      (node (ref "C15") (pin "1") (pinfunction "1_1") (pintype "passive"))
      (node (ref "C2") (pin "1") (pinfunction "1_1") (pintype "passive"))
      (node (ref "C3") (pin "1") (pinfunction "1_1") (pintype "passive"))
      (node (ref "C4") (pin "1") (pinfunction "1_1") (pintype "passive"))
      (node (ref "R10") (pin "2") (pinfunction "2_2") (pintype "passive"))
      (node (ref "R11") (pin "2") (pinfunction "2_2") (pintype "passive"))
      (node (ref "R14") (pin "2") (pinfunction "2_2") (pintype "passive"))
      (node (ref "R15") (pin "2") (pinfunction "2_2") (pintype "passive"))
      (node (ref "R16") (pin "2") (pinfunction "2_2") (pintype "passive"))
      (node (ref "R21") (pin "2") (pinfunction "2_2") (pintype "passive"))
      (node (ref "R48") (pin "2") (pinfunction "2_2") (pintype "passive"))
      (node (ref "R5") (pin "2") (pinfunction "2_2") (pintype "passive"))
      (node (ref "R6") (pin "2") (pinfunction "2_2") (pintype "passive"))
      (node (ref "R7") (pin "2") (pinfunction "2_2") (pintype "passive"))
      (node (ref "R8") (pin "2") (pinfunction "2_2") (pintype "passive"))
      (node (ref "R9") (pin "2") (pinfunction "2_2") (pintype "passive"))
      (node (ref "U1") (pin "9") (pinfunction "VDD_9") (pintype "passive"))
      (node (ref "U2") (pin "2") (pinfunction "VDD_2") (pintype "passive"))
      (node (ref "U4") (pin "2") (pinfunction "VOUT_2") (pintype "power_in"))
      (node (ref "U4") (pin "4") (pinfunction "TAB_4") (pintype "power_in"))
    )
    (net (code "26") (name "5V0") (class "Default")
      (node (ref "C10") (pin "1") (pinfunction "1_1") (pintype "passive"))
      (node (ref "C35") (pin "1") (pinfunction "1_1") (pintype "passive"))
      (node (ref "CN1") (pin "4") (pinfunction "4_4") (pintype "passive"))
      (node (ref "L1") (pin "2") (pinfunction "2_2") (pintype "passive"))
      (node (ref "R18") (pin "1") (pinfunction "1_1") (pintype "passive"))
      (node (ref "U10") (pin "6") (pinfunction "VOS_6") (pintype "passive"))
      (node (ref "U4") (pin "3") (pinfunction "VIN_3") (pintype "power_in"))
    )
    (net (code "27") (name "GND") (class "Default")
      (node (ref "C1") (pin "2") (pinfunction "2_2") (pintype "passive"))
      (node (ref "C10") (pin "2") (pinfunction "2_2") (pintype "passive"))
      (node (ref "C11") (pin "2") (pinfunction "2_2") (pintype "passive"))
      (node (ref "C12") (pin "2") (pinfunction "2_2") (pintype "passive"))
      (node (ref "C13") (pin "2") (pinfunction "2_2") (pintype "passive"))
      (node (ref "C14") (pin "2") (pinfunction "2_2") (pintype "passive"))
      (node (ref "C15") (pin "2") (pinfunction "2_2") (pintype "passive"))
      (node (ref "C16") (pin "2") (pinfunction "2_2") (pintype "passive"))
      (node (ref "C2") (pin "2") (pinfunction "2_2") (pintype "passive"))
      (node (ref "C27") (pin "2") (pinfunction "2_2") (pintype "passive"))
      (node (ref "C3") (pin "2") (pinfunction "2_2") (pintype "passive"))
      (node (ref "C31") (pin "2") (pinfunction "2_2") (pintype "passive"))
      (node (ref "C32") (pin "2") (pinfunction "2_2") (pintype "passive"))
      (node (ref "C34") (pin "2") (pinfunction "2_2") (pintype "passive"))
      (node (ref "C35") (pin "2") (pinfunction "2_2") (pintype "passive"))
      (node (ref "C36") (pin "2") (pinfunction "2_2") (pintype "passive"))
      (node (ref "C37") (pin "2") (pinfunction "2_2") (pintype "passive"))
      (node (ref "C39") (pin "2") (pinfunction "2_2") (pintype "passive"))
      (node (ref "C4") (pin "2") (pinfunction "2_2") (pintype "passive"))
      (node (ref "C40") (pin "2") (pinfunction "2_2") (pintype "passive"))
      (node (ref "C41") (pin "2") (pinfunction "2_2") (pintype "passive"))
      (node (ref "C7") (pin "2") (pinfunction "2_2") (pintype "passive"))
      (node (ref "C8") (pin "2") (pinfunction "2_2") (pintype "passive"))
      (node (ref "C9") (pin "2") (pinfunction "2_2") (pintype "passive"))
      (node (ref "CN1") (pin "15") (pinfunction "15_15") (pintype "passive"))
      (node (ref "CN1") (pin "16") (pinfunction "16_16") (pintype "passive"))
      (node (ref "CN1") (pin "7") (pinfunction "7_7") (pintype "passive"))
      (node (ref "CN1") (pin "8") (pinfunction "8_8") (pintype "passive"))
      (node (ref "CN2") (pin "2") (pinfunction "2_2") (pintype "power_in"))
      (node (ref "CN2") (pin "3") (pinfunction "3_3") (pintype "power_in"))
      (node (ref "CS1") (pin "2") (pinfunction "GND_2") (pintype "passive"))
      (node (ref "GND1") (pin "1") (pinfunction "1_1") (pintype "passive"))
      (node (ref "GND2") (pin "1") (pinfunction "1_1") (pintype "passive"))
      (node (ref "GND3") (pin "1") (pinfunction "1_1") (pintype "passive"))
      (node (ref "LED1") (pin "2") (pinfunction "2_2") (pintype "passive"))
      (node (ref "Q1") (pin "1") (pinfunction "G_1") (pintype "passive"))
      (node (ref "Q3") (pin "2") (pinfunction "E_2") (pintype "passive"))
      (node (ref "R12") (pin "2") (pinfunction "2_2") (pintype "passive"))
      (node (ref "R37") (pin "1") (pinfunction "1_1") (pintype "passive"))
      (node (ref "R46") (pin "1") (pinfunction "1_1") (pintype "passive"))
      (node (ref "R49") (pin "1") (pinfunction "1_1") (pintype "passive"))
      (node (ref "S1") (pin "2") (pinfunction "C_2") (pintype "passive"))
      (node (ref "S1") (pin "4") (pinfunction "F1_4") (pintype "passive"))
      (node (ref "S1") (pin "5") (pinfunction "S1_5") (pintype "passive"))
      (node (ref "S1") (pin "7") (pinfunction "F2_7") (pintype "passive"))
      (node (ref "S5") (pin "2") (pinfunction "C_2") (pintype "passive"))
      (node (ref "S5") (pin "4") (pinfunction "F1_4") (pintype "passive"))
      (node (ref "S5") (pin "5") (pinfunction "S1_5") (pintype "passive"))
      (node (ref "S5") (pin "7") (pinfunction "F2_7") (pintype "passive"))
      (node (ref "U1") (pin "10") (pinfunction "VSS_10") (pintype "passive"))
      (node (ref "U1") (pin "15") (pinfunction "A0_15") (pintype "passive"))
      (node (ref "U1") (pin "16") (pinfunction "A1_16") (pintype "passive"))
      (node (ref "U1") (pin "17") (pinfunction "A2_17") (pintype "passive"))
      (node (ref "U10") (pin "1") (pinfunction "PGND_1") (pintype "power_in"))
      (node (ref "U10") (pin "4") (pinfunction "AGND_4") (pintype "power_in"))
      (node (ref "U10") (pin "5") (pinfunction "FB_5") (pintype "passive"))
      (node (ref "U10") (pin "9") (pinfunction "PAD_9") (pintype "power_in"))
      (node (ref "U2") (pin "1") (pinfunction "VSS_1") (pintype "passive"))
      (node (ref "U2") (pin "10") (pinfunction "D3_10") (pintype "passive"))
      (node (ref "U2") (pin "11") (pinfunction "D4_11") (pintype "passive"))
      (node (ref "U2") (pin "12") (pinfunction "D5_12") (pintype "passive"))
      (node (ref "U2") (pin "13") (pinfunction "D6_13") (pintype "passive"))
      (node (ref "U2") (pin "14") (pinfunction "D7_14") (pintype "passive"))
      (node (ref "U2") (pin "19") (pinfunction "BS1_19") (pintype "passive"))
      (node (ref "U2") (pin "20") (pinfunction "BS0_20") (pintype "passive"))
      (node (ref "U2") (pin "5") (pinfunction "R/W_5") (pintype "passive"))
      (node (ref "U2") (pin "6") (pinfunction "E_6") (pintype "passive"))
      (node (ref "U3") (pin "2") (pinfunction "GND_2") (pintype "power_in"))
      (node (ref "U3") (pin "4") (pinfunction "PAD_4") (pintype "passive"))
      (node (ref "U4") (pin "1") (pinfunction "GND_1") (pintype "power_in"))
      (node (ref "U7") (pin "2") (pinfunction "VSS_2") (pintype "passive"))
      (node (ref "U7") (pin "6") (pinfunction "TIME_6") (pintype "passive"))
    )
    (net (code "28") (name "Net-(CN2-Pad1)") (class "Default")
      (node (ref "CN2") (pin "1") (pinfunction "1_1") (pintype "power_in"))
      (node (ref "F1") (pin "1") (pinfunction "1_1") (pintype "power_in"))
      (node (ref "R46") (pin "2") (pinfunction "2_2") (pintype "passive"))
    )
    (net (code "29") (name "Net-(CS1-SENSE)") (class "Default")
      (node (ref "CS1") (pin "1") (pinfunction "SENSE_1") (pintype "passive"))
      (node (ref "R50") (pin "1") (pinfunction "1_1") (pintype "passive"))
    )
    (net (code "30") (name "Net-(J1-Jack)") (class "Default")
      (node (ref "C5") (pin "2") (pinfunction "2_2") (pintype "passive"))
      (node (ref "C6") (pin "2") (pinfunction "2_2") (pintype "passive"))
      (node (ref "CN4") (pin "10") (pinfunction "10_10") (pintype "passive"))
      (node (ref "CN4") (pin "4") (pinfunction "4_4") (pintype "passive"))
      (node (ref "CN4") (pin "5") (pinfunction "5_5") (pintype "passive"))
      (node (ref "CN4") (pin "9") (pinfunction "9_9") (pintype "passive"))
      (node (ref "J1") (pin "1") (pinfunction "Jack_1") (pintype "passive"))
      (node (ref "R17") (pin "1") (pinfunction "1_1") (pintype "passive"))
    )
    (net (code "31") (name "Net-(J2-Jack)") (class "Default")
      (node (ref "C5") (pin "1") (pinfunction "1_1") (pintype "passive"))
      (node (ref "C6") (pin "1") (pinfunction "1_1") (pintype "passive"))
      (node (ref "CN4") (pin "1") (pinfunction "1_1") (pintype "passive"))
      (node (ref "CN4") (pin "2") (pinfunction "2_2") (pintype "passive"))
      (node (ref "CN4") (pin "3") (pinfunction "3_3") (pintype "passive"))
      (node (ref "CN4") (pin "6") (pinfunction "6_6") (pintype "passive"))
      (node (ref "CN4") (pin "7") (pinfunction "7_7") (pintype "passive"))
      (node (ref "CN4") (pin "8") (pinfunction "8_8") (pintype "passive"))
      (node (ref "J2") (pin "1") (pinfunction "Jack_1") (pintype "passive"))
      (node (ref "R17") (pin "2") (pinfunction "2_2") (pintype "passive"))
    )
    (net (code "32") (name "Net-(LED1-Pad1)") (class "Default")
      (node (ref "LED1") (pin "1") (pinfunction "1_1") (pintype "passive"))
      (node (ref "R21") (pin "1") (pinfunction "1_1") (pintype "passive"))
    )
    (net (code "33") (name "Net-(Q1-D)") (class "Default")
      (node (ref "F1") (pin "2") (pinfunction "2_2") (pintype "power_in"))
      (node (ref "Q1") (pin "3") (pinfunction "D_3") (pintype "passive"))
    )
    (net (code "34") (name "Net-(Q1-S)") (class "Default")
      (node (ref "C11") (pin "1") (pinfunction "1_1") (pintype "passive"))
      (node (ref "C7") (pin "1") (pinfunction "1_1") (pintype "passive"))
      (node (ref "FB1") (pin "1") (pinfunction "1_1") (pintype "passive"))
      (node (ref "Q1") (pin "2") (pinfunction "S_2") (pintype "passive"))
    )
    (net (code "35") (name "Net-(Q2-G)") (class "Default")
      (node (ref "Q2") (pin "1") (pinfunction "G_1") (pintype "passive"))
      (node (ref "Q3") (pin "3") (pinfunction "C_3") (pintype "passive"))
      (node (ref "R1") (pin "1") (pinfunction "1_1") (pintype "passive"))
    )
    (net (code "36") (name "Net-(Q3-B)") (class "Default")
      (node (ref "Q3") (pin "1") (pinfunction "B_1") (pintype "passive"))
      (node (ref "R12") (pin "1") (pinfunction "1_1") (pintype "passive"))
      (node (ref "R2") (pin "1") (pinfunction "1_1") (pintype "passive"))
    )
    (net (code "37") (name "Net-(S1-A)") (class "Default")
      (node (ref "R41") (pin "1") (pinfunction "1_1") (pintype "passive"))
      (node (ref "R7") (pin "1") (pinfunction "1_1") (pintype "passive"))
      (node (ref "S1") (pin "1") (pinfunction "A_1") (pintype "passive"))
    )
    (net (code "38") (name "Net-(S1-B)") (class "Default")
      (node (ref "R43") (pin "1") (pinfunction "1_1") (pintype "passive"))
      (node (ref "R5") (pin "1") (pinfunction "1_1") (pintype "passive"))
      (node (ref "S1") (pin "3") (pinfunction "B_3") (pintype "passive"))
    )
    (net (code "39") (name "Net-(S1-S2)") (class "Default")
      (node (ref "R42") (pin "2") (pinfunction "2_2") (pintype "passive"))
      (node (ref "R6") (pin "1") (pinfunction "1_1") (pintype "passive"))
      (node (ref "S1") (pin "6") (pinfunction "S2_6") (pintype "passive"))
    )
    (net (code "40") (name "Net-(S5-A)") (class "Default")
      (node (ref "R16") (pin "1") (pinfunction "1_1") (pintype "passive"))
      (node (ref "R27") (pin "1") (pinfunction "1_1") (pintype "passive"))
      (node (ref "S5") (pin "1") (pinfunction "A_1") (pintype "passive"))
    )
    (net (code "41") (name "Net-(S5-B)") (class "Default")
      (node (ref "R14") (pin "1") (pinfunction "1_1") (pintype "passive"))
      (node (ref "R28") (pin "1") (pinfunction "1_1") (pintype "passive"))
      (node (ref "S5") (pin "3") (pinfunction "B_3") (pintype "passive"))
    )
    (net (code "42") (name "Net-(S5-S2)") (class "Default")
      (node (ref "R15") (pin "1") (pinfunction "1_1") (pintype "passive"))
      (node (ref "R45") (pin "2") (pinfunction "2_2") (pintype "passive"))
      (node (ref "S5") (pin "6") (pinfunction "S2_6") (pintype "passive"))
    )
    (net (code "43") (name "Net-(U3-VOUT)") (class "Default")
      (node (ref "C16") (pin "1") (pinfunction "1_1") (pintype "passive"))
      (node (ref "C41") (pin "1") (pinfunction "1_1") (pintype "passive"))
      (node (ref "U3") (pin "3") (pinfunction "VOUT_3") (pintype "passive"))
      (node (ref "U7") (pin "5") (pinfunction "VDD_5") (pintype "passive"))
    )
    (net (code "44") (name "Net-(U7-OUT)") (class "Default")
      (node (ref "R2") (pin "2") (pinfunction "2_2") (pintype "passive"))
      (node (ref "U7") (pin "1") (pinfunction "OUT_1") (pintype "passive"))
    )
    (net (code "45") (name "Net-(U7-SNS)") (class "Default")
      (node (ref "C42") (pin "1") (pinfunction "1_1") (pintype "passive"))
      (node (ref "R49") (pin "2") (pinfunction "2_2") (pintype "passive"))
      (node (ref "U7") (pin "4") (pinfunction "SNS_4") (pintype "passive"))
    )
    (net (code "46") (name "Net-(U7-SNSK)") (class "Default")
      (node (ref "C42") (pin "2") (pinfunction "2_2") (pintype "passive"))
      (node (ref "R50") (pin "2") (pinfunction "2_2") (pintype "passive"))
      (node (ref "U7") (pin "3") (pinfunction "SNSK_3") (pintype "passive"))
    )
    (net (code "47") (name "Net-(U10-PG)") (class "Default")
      (node (ref "R18") (pin "2") (pinfunction "2_2") (pintype "passive"))
      (node (ref "U10") (pin "8") (pinfunction "PG_8") (pintype "passive"))
    )
    (net (code "48") (name "Net-(U10-SW)") (class "Default")
      (node (ref "L1") (pin "1") (pinfunction "1_1") (pintype "passive"))
      (node (ref "U10") (pin "7") (pinfunction "SW_7") (pintype "passive"))
    )
    (net (code "49") (name "unconnected-(U1-GPA7-Pad28)") (class "Default")
      (node (ref "U1") (pin "28") (pinfunction "GPA7_28") (pintype "passive+no_connect"))
    )
    (net (code "50") (name "unconnected-(U1-GPB0-Pad1)") (class "Default")
      (node (ref "U1") (pin "1") (pinfunction "GPB0_1") (pintype "passive+no_connect"))
    )
    (net (code "51") (name "unconnected-(U1-GPB1-Pad2)") (class "Default")
      (node (ref "U1") (pin "2") (pinfunction "GPB1_2") (pintype "passive+no_connect"))
    )
    (net (code "52") (name "unconnected-(U1-GPB2-Pad3)") (class "Default")
      (node (ref "U1") (pin "3") (pinfunction "GPB2_3") (pintype "passive"))
    )
    (net (code "53") (name "unconnected-(U1-GPB3-Pad4)") (class "Default")
      (node (ref "U1") (pin "4") (pinfunction "GPB3_4") (pintype "passive"))
    )
    (net (code "54") (name "unconnected-(U1-GPB4-Pad5)") (class "Default")
      (node (ref "U1") (pin "5") (pinfunction "GPB4_5") (pintype "passive+no_connect"))
    )
    (net (code "55") (name "unconnected-(U1-GPB5-Pad6)") (class "Default")
      (node (ref "U1") (pin "6") (pinfunction "GPB5_6") (pintype "passive"))
    )
    (net (code "56") (name "unconnected-(U1-GPB6-Pad7)") (class "Default")
      (node (ref "U1") (pin "7") (pinfunction "GPB6_7") (pintype "passive+no_connect"))
    )
    (net (code "57") (name "unconnected-(U1-GPB7-Pad8)") (class "Default")
      (node (ref "U1") (pin "8") (pinfunction "GPB7_8") (pintype "passive+no_connect"))
    )
    (net (code "58") (name "unconnected-(U1-NC-Pad11)") (class "Default")
      (node (ref "U1") (pin "11") (pinfunction "NC_11") (pintype "passive+no_connect"))
    )
    (net (code "59") (name "unconnected-(U1-NC-Pad14)") (class "Default")
      (node (ref "U1") (pin "14") (pinfunction "NC_14") (pintype "passive+no_connect"))
    )
    (net (code "60") (name "unconnected-(U2-D2-Pad9)") (class "Default")
      (node (ref "U2") (pin "9") (pinfunction "D2_9") (pintype "passive+no_connect"))
    )
    (net (code "61") (name "unconnected-(U2-NC-Pad3)") (class "Default")
      (node (ref "U2") (pin "3") (pinfunction "NC_3") (pintype "passive+no_connect"))
    )
    (net (code "62") (name "unconnected-(U2-NC-Pad15)") (class "Default")
      (node (ref "U2") (pin "15") (pinfunction "NC_15") (pintype "passive+no_connect"))
    )
    (net (code "63") (name "unconnected-(U2-NC-Pad18)") (class "Default")
      (node (ref "U2") (pin "18") (pinfunction "NC_18") (pintype "passive+no_connect"))
    )
  )
)
